# isg_cena_chip_wirebonding_board.net
KiCad netlist of a schematic drawn in Altium Designer
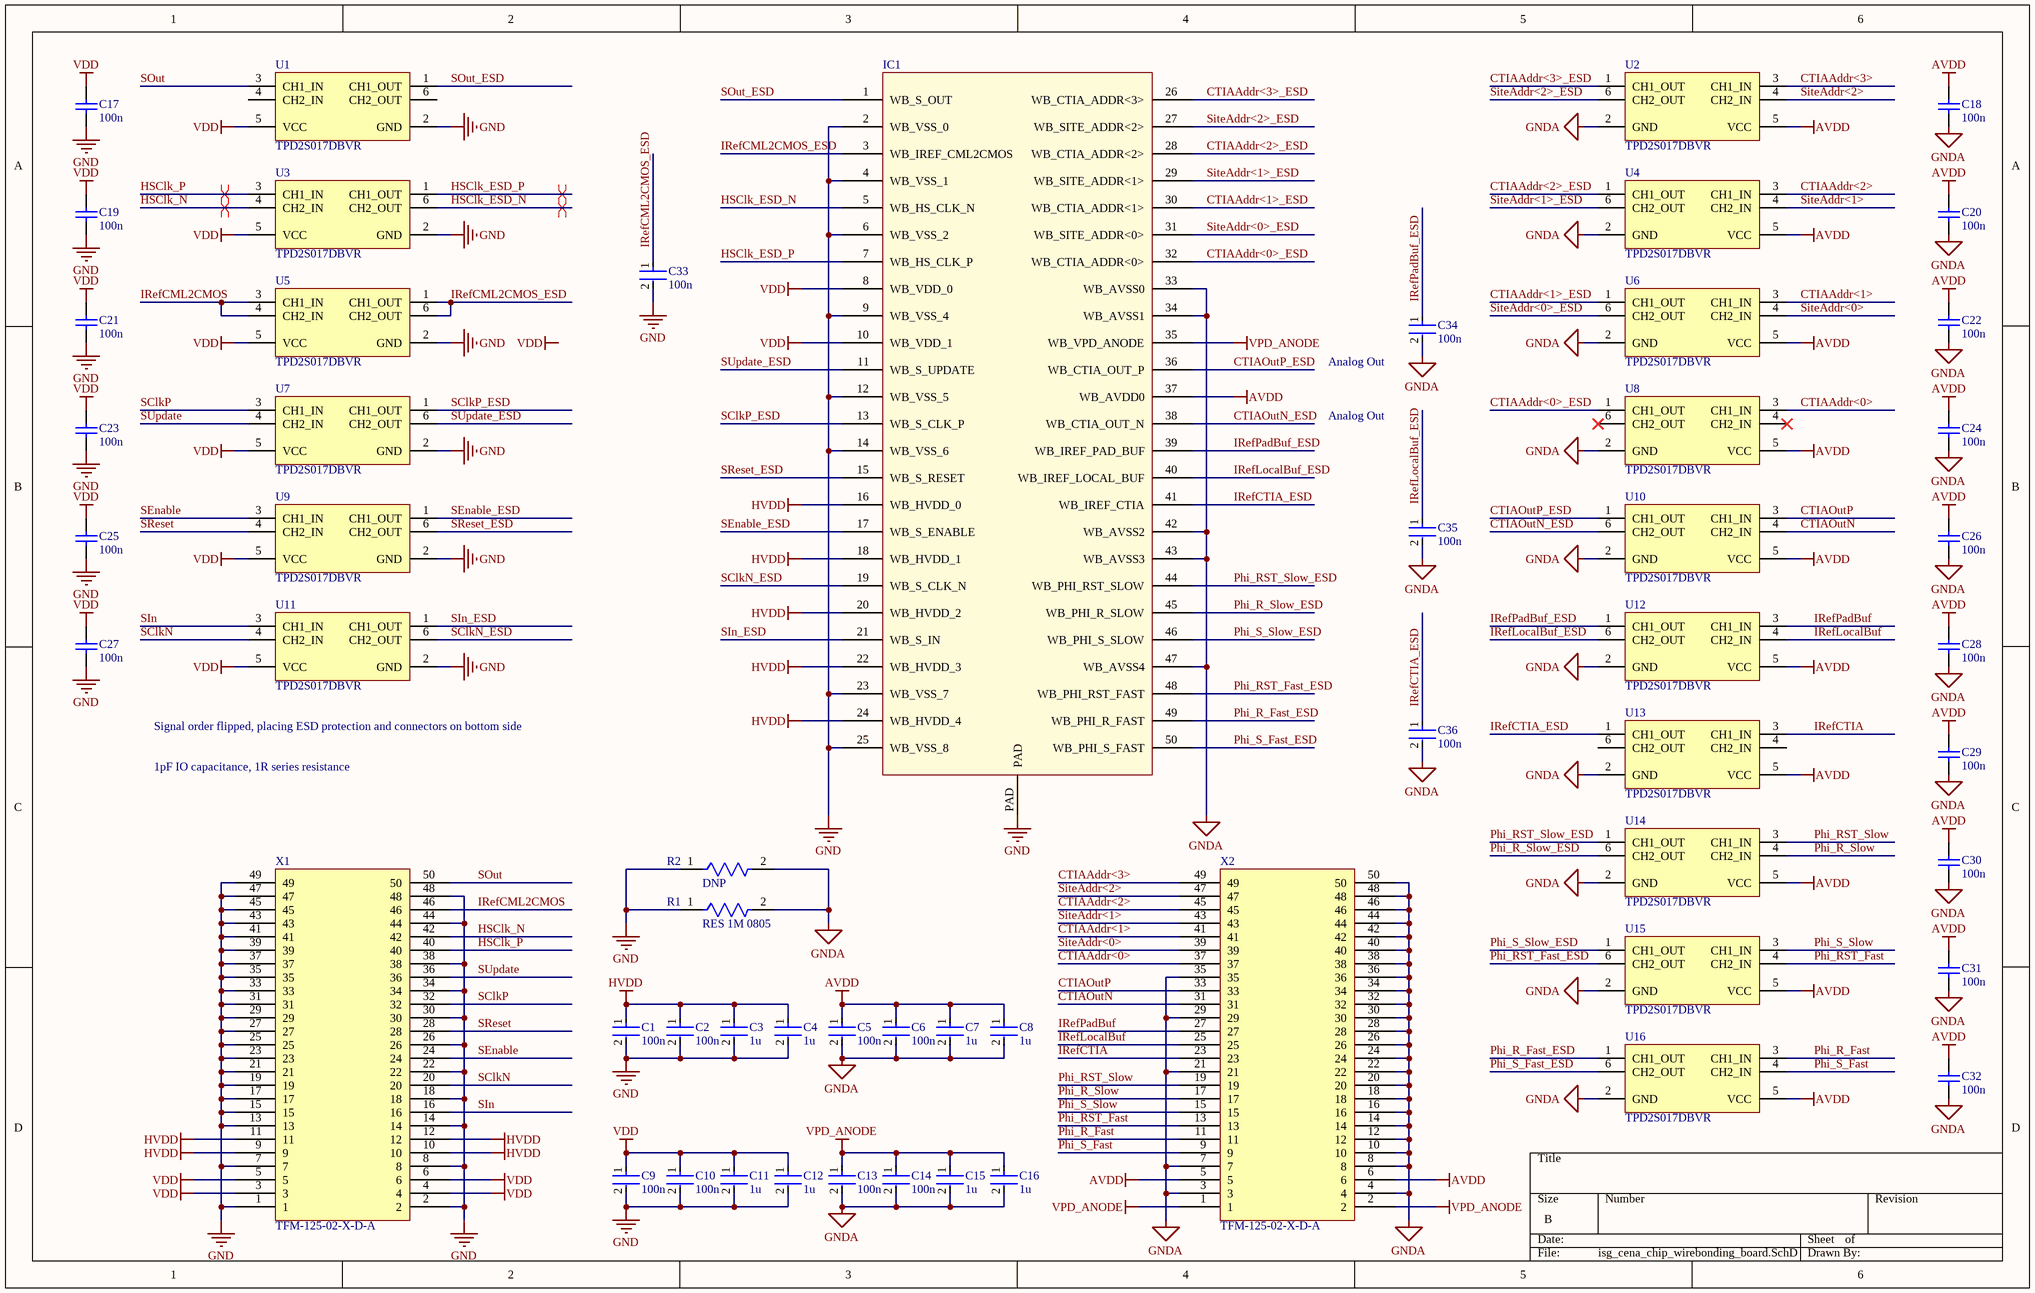
[diagram p0: isg_cena_chip_wirebonding_board.SchDoc]

(export (version "E")
  (design (tool "Eeschema 10.0.6"))
  (components
    (comp (ref "C1")
      (value "100n")
      (footprint "FP-0603-L_1_6_0_15-W_0_8-IPC_C")
      (description "Ceramic Capacitor General Use 1uF ±10% 50V X7R 0603")
      (fields (field (name "TOLERANCE") "10%"))
      (libsource (lib "Altium Content Vault") (part "11868f565c42a9108669ba33697ecf6"))
    )
    (comp (ref "C2")
      (value "100n")
      (footprint "FP-0603-L_1_6_0_15-W_0_8-IPC_C")
      (description "Ceramic Capacitor General Use 1uF ±10% 50V X7R 0603")
      (fields (field (name "TOLERANCE") "10%"))
      (libsource (lib "Altium Content Vault") (part "11868f565c42a9108669ba33697ecf6"))
    )
    (comp (ref "C3")
      (value "1u")
      (footprint "FP-0603-L_1_6_0_15-W_0_8-IPC_C")
      (description "Ceramic Capacitor General Use 1uF ±10% 50V X7R 0603")
      (fields (field (name "TOLERANCE") "10%"))
      (libsource (lib "Altium Content Vault") (part "11868f565c42a9108669ba33697ecf6"))
    )
    (comp (ref "C4")
      (value "1u")
      (footprint "FP-0603-L_1_6_0_15-W_0_8-IPC_C")
      (description "Ceramic Capacitor General Use 1uF ±10% 50V X7R 0603")
      (fields (field (name "TOLERANCE") "10%"))
      (libsource (lib "Altium Content Vault") (part "11868f565c42a9108669ba33697ecf6"))
    )
    (comp (ref "C5")
      (value "100n")
      (footprint "FP-0603-L_1_6_0_15-W_0_8-IPC_C")
      (description "Ceramic Capacitor General Use 1uF ±10% 50V X7R 0603")
      (fields (field (name "TOLERANCE") "10%"))
      (libsource (lib "Altium Content Vault") (part "11868f565c42a9108669ba33697ecf6"))
    )
    (comp (ref "C6")
      (value "100n")
      (footprint "FP-0603-L_1_6_0_15-W_0_8-IPC_C")
      (description "Ceramic Capacitor General Use 1uF ±10% 50V X7R 0603")
      (fields (field (name "TOLERANCE") "10%"))
      (libsource (lib "Altium Content Vault") (part "11868f565c42a9108669ba33697ecf6"))
    )
    (comp (ref "C7")
      (value "1u")
      (footprint "FP-0603-L_1_6_0_15-W_0_8-IPC_C")
      (description "Ceramic Capacitor General Use 1uF ±10% 50V X7R 0603")
      (fields (field (name "TOLERANCE") "10%"))
      (libsource (lib "Altium Content Vault") (part "11868f565c42a9108669ba33697ecf6"))
    )
    (comp (ref "C8")
      (value "1u")
      (footprint "FP-0603-L_1_6_0_15-W_0_8-IPC_C")
      (description "Ceramic Capacitor General Use 1uF ±10% 50V X7R 0603")
      (fields (field (name "TOLERANCE") "10%"))
      (libsource (lib "Altium Content Vault") (part "11868f565c42a9108669ba33697ecf6"))
    )
    (comp (ref "C9")
      (value "100n")
      (footprint "FP-0603-L_1_6_0_15-W_0_8-IPC_C")
      (description "Ceramic Capacitor General Use 1uF ±10% 50V X7R 0603")
      (fields (field (name "TOLERANCE") "10%"))
      (libsource (lib "Altium Content Vault") (part "11868f565c42a9108669ba33697ecf6"))
    )
    (comp (ref "C10")
      (value "100n")
      (footprint "FP-0603-L_1_6_0_15-W_0_8-IPC_C")
      (description "Ceramic Capacitor General Use 1uF ±10% 50V X7R 0603")
      (fields (field (name "TOLERANCE") "10%"))
      (libsource (lib "Altium Content Vault") (part "11868f565c42a9108669ba33697ecf6"))
    )
    (comp (ref "C11")
      (value "1u")
      (footprint "FP-0603-L_1_6_0_15-W_0_8-IPC_C")
      (description "Ceramic Capacitor General Use 1uF ±10% 50V X7R 0603")
      (fields (field (name "TOLERANCE") "10%"))
      (libsource (lib "Altium Content Vault") (part "11868f565c42a9108669ba33697ecf6"))
    )
    (comp (ref "C12")
      (value "1u")
      (footprint "FP-0603-L_1_6_0_15-W_0_8-IPC_C")
      (description "Ceramic Capacitor General Use 1uF ±10% 50V X7R 0603")
      (fields (field (name "TOLERANCE") "10%"))
      (libsource (lib "Altium Content Vault") (part "11868f565c42a9108669ba33697ecf6"))
    )
    (comp (ref "C13")
      (value "100n")
      (footprint "FP-0603-L_1_6_0_15-W_0_8-IPC_C")
      (description "Ceramic Capacitor General Use 1uF ±10% 50V X7R 0603")
      (fields (field (name "TOLERANCE") "10%"))
      (libsource (lib "Altium Content Vault") (part "11868f565c42a9108669ba33697ecf6"))
    )
    (comp (ref "C14")
      (value "100n")
      (footprint "FP-0603-L_1_6_0_15-W_0_8-IPC_C")
      (description "Ceramic Capacitor General Use 1uF ±10% 50V X7R 0603")
      (fields (field (name "TOLERANCE") "10%"))
      (libsource (lib "Altium Content Vault") (part "11868f565c42a9108669ba33697ecf6"))
    )
    (comp (ref "C15")
      (value "1u")
      (footprint "FP-0603-L_1_6_0_15-W_0_8-IPC_C")
      (description "Ceramic Capacitor General Use 1uF ±10% 50V X7R 0603")
      (fields (field (name "TOLERANCE") "10%"))
      (libsource (lib "Altium Content Vault") (part "11868f565c42a9108669ba33697ecf6"))
    )
    (comp (ref "C16")
      (value "1u")
      (footprint "FP-0603-L_1_6_0_15-W_0_8-IPC_C")
      (description "Ceramic Capacitor General Use 1uF ±10% 50V X7R 0603")
      (fields (field (name "TOLERANCE") "10%"))
      (libsource (lib "Altium Content Vault") (part "11868f565c42a9108669ba33697ecf6"))
    )
    (comp (ref "C17")
      (value "100n")
      (footprint "CAPC1050X55X23ML05T13")
      (description "Chip Capacitor, 100 nF, +/- 10%, 16 V, -55 to 125 degC, 0402 (1005 Metric), RoHS, Tape and Reel")
      (fields (field (name "MANUFACTURER") "Samsung Electro-Mechanics"))
      (libsource (lib "Altium Content Vault") (part "CAP-NP-2"))
    )
    (comp (ref "C18")
      (value "100n")
      (footprint "CAPC1050X55X23ML05T13")
      (description "Chip Capacitor, 100 nF, +/- 10%, 16 V, -55 to 125 degC, 0402 (1005 Metric), RoHS, Tape and Reel")
      (fields (field (name "MANUFACTURER") "Samsung Electro-Mechanics"))
      (libsource (lib "Altium Content Vault") (part "CAP-NP-2"))
    )
    (comp (ref "C19")
      (value "100n")
      (footprint "CAPC1050X55X23ML05T13")
      (description "Chip Capacitor, 100 nF, +/- 10%, 16 V, -55 to 125 degC, 0402 (1005 Metric), RoHS, Tape and Reel")
      (fields (field (name "MANUFACTURER") "Samsung Electro-Mechanics"))
      (libsource (lib "Altium Content Vault") (part "CAP-NP-2"))
    )
    (comp (ref "C20")
      (value "100n")
      (footprint "CAPC1050X55X23ML05T13")
      (description "Chip Capacitor, 100 nF, +/- 10%, 16 V, -55 to 125 degC, 0402 (1005 Metric), RoHS, Tape and Reel")
      (fields (field (name "MANUFACTURER") "Samsung Electro-Mechanics"))
      (libsource (lib "Altium Content Vault") (part "CAP-NP-2"))
    )
    (comp (ref "C21")
      (value "100n")
      (footprint "CAPC1050X55X23ML05T13")
      (description "Chip Capacitor, 100 nF, +/- 10%, 16 V, -55 to 125 degC, 0402 (1005 Metric), RoHS, Tape and Reel")
      (fields (field (name "MANUFACTURER") "Samsung Electro-Mechanics"))
      (libsource (lib "Altium Content Vault") (part "CAP-NP-2"))
    )
    (comp (ref "C22")
      (value "100n")
      (footprint "CAPC1050X55X23ML05T13")
      (description "Chip Capacitor, 100 nF, +/- 10%, 16 V, -55 to 125 degC, 0402 (1005 Metric), RoHS, Tape and Reel")
      (fields (field (name "MANUFACTURER") "Samsung Electro-Mechanics"))
      (libsource (lib "Altium Content Vault") (part "CAP-NP-2"))
    )
    (comp (ref "C23")
      (value "100n")
      (footprint "CAPC1050X55X23ML05T13")
      (description "Chip Capacitor, 100 nF, +/- 10%, 16 V, -55 to 125 degC, 0402 (1005 Metric), RoHS, Tape and Reel")
      (fields (field (name "MANUFACTURER") "Samsung Electro-Mechanics"))
      (libsource (lib "Altium Content Vault") (part "CAP-NP-2"))
    )
    (comp (ref "C24")
      (value "100n")
      (footprint "CAPC1050X55X23ML05T13")
      (description "Chip Capacitor, 100 nF, +/- 10%, 16 V, -55 to 125 degC, 0402 (1005 Metric), RoHS, Tape and Reel")
      (fields (field (name "MANUFACTURER") "Samsung Electro-Mechanics"))
      (libsource (lib "Altium Content Vault") (part "CAP-NP-2"))
    )
    (comp (ref "C25")
      (value "100n")
      (footprint "CAPC1050X55X23ML05T13")
      (description "Chip Capacitor, 100 nF, +/- 10%, 16 V, -55 to 125 degC, 0402 (1005 Metric), RoHS, Tape and Reel")
      (fields (field (name "MANUFACTURER") "Samsung Electro-Mechanics"))
      (libsource (lib "Altium Content Vault") (part "CAP-NP-2"))
    )
    (comp (ref "C26")
      (value "100n")
      (footprint "CAPC1050X55X23ML05T13")
      (description "Chip Capacitor, 100 nF, +/- 10%, 16 V, -55 to 125 degC, 0402 (1005 Metric), RoHS, Tape and Reel")
      (fields (field (name "MANUFACTURER") "Samsung Electro-Mechanics"))
      (libsource (lib "Altium Content Vault") (part "CAP-NP-2"))
    )
    (comp (ref "C27")
      (value "100n")
      (footprint "CAPC1050X55X23ML05T13")
      (description "Chip Capacitor, 100 nF, +/- 10%, 16 V, -55 to 125 degC, 0402 (1005 Metric), RoHS, Tape and Reel")
      (fields (field (name "MANUFACTURER") "Samsung Electro-Mechanics"))
      (libsource (lib "Altium Content Vault") (part "CAP-NP-2"))
    )
    (comp (ref "C28")
      (value "100n")
      (footprint "CAPC1050X55X23ML05T13")
      (description "Chip Capacitor, 100 nF, +/- 10%, 16 V, -55 to 125 degC, 0402 (1005 Metric), RoHS, Tape and Reel")
      (fields (field (name "MANUFACTURER") "Samsung Electro-Mechanics"))
      (libsource (lib "Altium Content Vault") (part "CAP-NP-2"))
    )
    (comp (ref "C29")
      (value "100n")
      (footprint "CAPC1050X55X23ML05T13")
      (description "Chip Capacitor, 100 nF, +/- 10%, 16 V, -55 to 125 degC, 0402 (1005 Metric), RoHS, Tape and Reel")
      (fields (field (name "MANUFACTURER") "Samsung Electro-Mechanics"))
      (libsource (lib "Altium Content Vault") (part "CAP-NP-2"))
    )
    (comp (ref "C30")
      (value "100n")
      (footprint "CAPC1050X55X23ML05T13")
      (description "Chip Capacitor, 100 nF, +/- 10%, 16 V, -55 to 125 degC, 0402 (1005 Metric), RoHS, Tape and Reel")
      (fields (field (name "MANUFACTURER") "Samsung Electro-Mechanics"))
      (libsource (lib "Altium Content Vault") (part "CAP-NP-2"))
    )
    (comp (ref "C31")
      (value "100n")
      (footprint "CAPC1050X55X23ML05T13")
      (description "Chip Capacitor, 100 nF, +/- 10%, 16 V, -55 to 125 degC, 0402 (1005 Metric), RoHS, Tape and Reel")
      (fields (field (name "MANUFACTURER") "Samsung Electro-Mechanics"))
      (libsource (lib "Altium Content Vault") (part "CAP-NP-2"))
    )
    (comp (ref "C32")
      (value "100n")
      (footprint "CAPC1050X55X23ML05T13")
      (description "Chip Capacitor, 100 nF, +/- 10%, 16 V, -55 to 125 degC, 0402 (1005 Metric), RoHS, Tape and Reel")
      (fields (field (name "MANUFACTURER") "Samsung Electro-Mechanics"))
      (libsource (lib "Altium Content Vault") (part "CAP-NP-2"))
    )
    (comp (ref "C33")
      (value "100n")
      (footprint "FP-0603-L_1_6_0_15-W_0_8-IPC_C")
      (description "Ceramic Capacitor General Use 1uF ±10% 50V X7R 0603")
      (fields (field (name "TOLERANCE") "10%"))
      (libsource (lib "Altium Content Vault") (part "11868f565c42a9108669ba33697ecf6"))
    )
    (comp (ref "C34")
      (value "100n")
      (footprint "FP-0603-L_1_6_0_15-W_0_8-IPC_C")
      (description "Ceramic Capacitor General Use 1uF ±10% 50V X7R 0603")
      (fields (field (name "TOLERANCE") "10%"))
      (libsource (lib "Altium Content Vault") (part "11868f565c42a9108669ba33697ecf6"))
    )
    (comp (ref "C35")
      (value "100n")
      (footprint "FP-0603-L_1_6_0_15-W_0_8-IPC_C")
      (description "Ceramic Capacitor General Use 1uF ±10% 50V X7R 0603")
      (fields (field (name "TOLERANCE") "10%"))
      (libsource (lib "Altium Content Vault") (part "11868f565c42a9108669ba33697ecf6"))
    )
    (comp (ref "C36")
      (value "100n")
      (footprint "FP-0603-L_1_6_0_15-W_0_8-IPC_C")
      (description "Ceramic Capacitor General Use 1uF ±10% 50V X7R 0603")
      (fields (field (name "TOLERANCE") "10%"))
      (libsource (lib "Altium Content Vault") (part "11868f565c42a9108669ba33697ecf6"))
    )
    (comp (ref "IC1") (value "~") (footprint "Cena_WB_4/4") (libsource (lib "CenaChip") (part "Cena")))
    (comp (ref "R1")
      (value "RES 1M 0805")
      (footprint "FP-ERJ6EN-IPC_A")
      (description "RES SMD 1M OHM 1% 1/8W 0805")
      (fields (field (name "TOLERANCE") "1%"))
      (libsource (lib "Altium Content Vault") (part "1029c3af85768c4190bb7ad29bc67b5"))
    )
    (comp (ref "R2")
      (value "DNP")
      (footprint "FP-ERJ6EN-IPC_A")
      (fields (field (name "TOLERANCE") "1%"))
      (libsource (lib "Altium Content Vault") (part "1029c3af85768c4190bb7ad29bc67b5"))
    )
    (comp (ref "U1")
      (value "TPD2S017DBVR")
      (footprint "DBV0006A_L")
      (fields (field (name "MANUFACTURER") "Texas Instruments"))
      (libsource (lib "") (part "TI-TPD2S017-SOT-23_DBV-6_1"))
    )
    (comp (ref "U2")
      (value "TPD2S017DBVR")
      (footprint "DBV0006A_L")
      (fields (field (name "MANUFACTURER") "Texas Instruments"))
      (libsource (lib "Altium Content Vault") (part "TI-TPD2S017-SOT-23_DBV-6"))
    )
    (comp (ref "U3")
      (value "TPD2S017DBVR")
      (footprint "DBV0006A_L")
      (fields (field (name "MANUFACTURER") "Texas Instruments"))
      (libsource (lib "") (part "TI-TPD2S017-SOT-23_DBV-6_1"))
    )
    (comp (ref "U4")
      (value "TPD2S017DBVR")
      (footprint "DBV0006A_L")
      (fields (field (name "MANUFACTURER") "Texas Instruments"))
      (libsource (lib "Altium Content Vault") (part "TI-TPD2S017-SOT-23_DBV-6"))
    )
    (comp (ref "U5")
      (value "TPD2S017DBVR")
      (footprint "DBV0006A_L")
      (fields (field (name "MANUFACTURER") "Texas Instruments"))
      (libsource (lib "") (part "TI-TPD2S017-SOT-23_DBV-6_1"))
    )
    (comp (ref "U6")
      (value "TPD2S017DBVR")
      (footprint "DBV0006A_L")
      (fields (field (name "MANUFACTURER") "Texas Instruments"))
      (libsource (lib "Altium Content Vault") (part "TI-TPD2S017-SOT-23_DBV-6"))
    )
    (comp (ref "U7")
      (value "TPD2S017DBVR")
      (footprint "DBV0006A_L")
      (fields (field (name "MANUFACTURER") "Texas Instruments"))
      (libsource (lib "") (part "TI-TPD2S017-SOT-23_DBV-6_1"))
    )
    (comp (ref "U8")
      (value "TPD2S017DBVR")
      (footprint "DBV0006A_L")
      (fields (field (name "MANUFACTURER") "Texas Instruments"))
      (libsource (lib "Altium Content Vault") (part "TI-TPD2S017-SOT-23_DBV-6"))
    )
    (comp (ref "U9")
      (value "TPD2S017DBVR")
      (footprint "DBV0006A_L")
      (fields (field (name "MANUFACTURER") "Texas Instruments"))
      (libsource (lib "") (part "TI-TPD2S017-SOT-23_DBV-6_1"))
    )
    (comp (ref "U10")
      (value "TPD2S017DBVR")
      (footprint "DBV0006A_L")
      (fields (field (name "MANUFACTURER") "Texas Instruments"))
      (libsource (lib "Altium Content Vault") (part "TI-TPD2S017-SOT-23_DBV-6"))
    )
    (comp (ref "U11")
      (value "TPD2S017DBVR")
      (footprint "DBV0006A_L")
      (fields (field (name "MANUFACTURER") "Texas Instruments"))
      (libsource (lib "") (part "TI-TPD2S017-SOT-23_DBV-6_1"))
    )
    (comp (ref "U12")
      (value "TPD2S017DBVR")
      (footprint "DBV0006A_L")
      (fields (field (name "MANUFACTURER") "Texas Instruments"))
      (libsource (lib "Altium Content Vault") (part "TI-TPD2S017-SOT-23_DBV-6"))
    )
    (comp (ref "U13")
      (value "TPD2S017DBVR")
      (footprint "DBV0006A_L")
      (fields (field (name "MANUFACTURER") "Texas Instruments"))
      (libsource (lib "Altium Content Vault") (part "TI-TPD2S017-SOT-23_DBV-6"))
    )
    (comp (ref "U14")
      (value "TPD2S017DBVR")
      (footprint "DBV0006A_L")
      (fields (field (name "MANUFACTURER") "Texas Instruments"))
      (libsource (lib "Altium Content Vault") (part "TI-TPD2S017-SOT-23_DBV-6"))
    )
    (comp (ref "U15")
      (value "TPD2S017DBVR")
      (footprint "DBV0006A_L")
      (fields (field (name "MANUFACTURER") "Texas Instruments"))
      (libsource (lib "Altium Content Vault") (part "TI-TPD2S017-SOT-23_DBV-6"))
    )
    (comp (ref "U16")
      (value "TPD2S017DBVR")
      (footprint "DBV0006A_L")
      (fields (field (name "MANUFACTURER") "Texas Instruments"))
      (libsource (lib "Altium Content Vault") (part "TI-TPD2S017-SOT-23_DBV-6"))
    )
    (comp (ref "X1")
      (value "TFM-125-02-X-D-A")
      (footprint "SAMTEC-TFM-125-02-X-D-A")
      (description "SAMTEC TFM-125-02-X-D-A")
      (libsource (lib "SAMTEC-TFM-125-02-X-D-A") (part "TFM-125-02-X-D-A"))
    )
    (comp (ref "X2")
      (value "TFM-125-02-X-D-A")
      (footprint "SAMTEC-TFM-125-02-X-D-A")
      (description "SAMTEC TFM-125-02-X-D-A")
      (libsource (lib "SAMTEC-TFM-125-02-X-D-A") (part "TFM-125-02-X-D-A"))
    )
  )
  (nets
    (net (code "1") (name "/CTIAAddr<0>") (class "Default")
      (node (ref "U8") (pin "3") (pinfunction "CH1_IN_3") (pintype "passive"))
      (node (ref "X2") (pin "37") (pinfunction "37_37") (pintype "passive"))
    )
    (net (code "2") (name "/CTIAAddr<0>_ESD") (class "Default")
      (node (ref "IC1") (pin "32") (pinfunction "WB_CTIA_ADDR<0>_32") (pintype "passive"))
      (node (ref "U8") (pin "1") (pinfunction "CH1_OUT_1") (pintype "passive"))
    )
    (net (code "3") (name "/CTIAAddr<1>") (class "Default")
      (node (ref "U6") (pin "3") (pinfunction "CH1_IN_3") (pintype "passive"))
      (node (ref "X2") (pin "41") (pinfunction "41_41") (pintype "passive"))
    )
    (net (code "4") (name "/CTIAAddr<1>_ESD") (class "Default")
      (node (ref "IC1") (pin "30") (pinfunction "WB_CTIA_ADDR<1>_30") (pintype "passive"))
      (node (ref "U6") (pin "1") (pinfunction "CH1_OUT_1") (pintype "passive"))
    )
    (net (code "5") (name "/CTIAAddr<2>") (class "Default")
      (node (ref "U4") (pin "3") (pinfunction "CH1_IN_3") (pintype "passive"))
      (node (ref "X2") (pin "45") (pinfunction "45_45") (pintype "passive"))
    )
    (net (code "6") (name "/CTIAAddr<2>_ESD") (class "Default")
      (node (ref "IC1") (pin "28") (pinfunction "WB_CTIA_ADDR<2>_28") (pintype "passive"))
      (node (ref "U4") (pin "1") (pinfunction "CH1_OUT_1") (pintype "passive"))
    )
    (net (code "7") (name "/CTIAAddr<3>") (class "Default")
      (node (ref "U2") (pin "3") (pinfunction "CH1_IN_3") (pintype "passive"))
      (node (ref "X2") (pin "49") (pinfunction "49_49") (pintype "passive"))
    )
    (net (code "8") (name "/CTIAAddr<3>_ESD") (class "Default")
      (node (ref "IC1") (pin "26") (pinfunction "WB_CTIA_ADDR<3>_26") (pintype "passive"))
      (node (ref "U2") (pin "1") (pinfunction "CH1_OUT_1") (pintype "passive"))
    )
    (net (code "9") (name "/CTIAOutN") (class "Default")
      (node (ref "U10") (pin "4") (pinfunction "CH2_IN_4") (pintype "passive"))
      (node (ref "X2") (pin "31") (pinfunction "31_31") (pintype "passive"))
    )
    (net (code "10") (name "/CTIAOutN_ESD") (class "Default")
      (node (ref "IC1") (pin "38") (pinfunction "WB_CTIA_OUT_N_38") (pintype "passive"))
      (node (ref "U10") (pin "6") (pinfunction "CH2_OUT_6") (pintype "passive"))
    )
    (net (code "11") (name "/CTIAOutP") (class "Default")
      (node (ref "U10") (pin "3") (pinfunction "CH1_IN_3") (pintype "passive"))
      (node (ref "X2") (pin "33") (pinfunction "33_33") (pintype "passive"))
    )
    (net (code "12") (name "/CTIAOutP_ESD") (class "Default")
      (node (ref "IC1") (pin "36") (pinfunction "WB_CTIA_OUT_P_36") (pintype "passive"))
      (node (ref "U10") (pin "1") (pinfunction "CH1_OUT_1") (pintype "passive"))
    )
    (net (code "13") (name "/HSClk_ESD_N") (class "Default")
      (node (ref "IC1") (pin "5") (pinfunction "WB_HS_CLK_N_5") (pintype "passive"))
      (node (ref "U3") (pin "6") (pinfunction "CH2_OUT_6") (pintype "passive"))
    )
    (net (code "14") (name "/HSClk_ESD_P") (class "Default")
      (node (ref "IC1") (pin "7") (pinfunction "WB_HS_CLK_P_7") (pintype "passive"))
      (node (ref "U3") (pin "1") (pinfunction "CH1_OUT_1") (pintype "passive"))
    )
    (net (code "15") (name "/HSClk_N") (class "Default")
      (node (ref "U3") (pin "4") (pinfunction "CH2_IN_4") (pintype "passive"))
      (node (ref "X1") (pin "42") (pinfunction "42_42") (pintype "passive"))
    )
    (net (code "16") (name "/HSClk_P") (class "Default")
      (node (ref "U3") (pin "3") (pinfunction "CH1_IN_3") (pintype "passive"))
      (node (ref "X1") (pin "40") (pinfunction "40_40") (pintype "passive"))
    )
    (net (code "17") (name "/IRefCML2CMOS") (class "Default")
      (node (ref "U5") (pin "3") (pinfunction "CH1_IN_3") (pintype "passive"))
      (node (ref "U5") (pin "4") (pinfunction "CH2_IN_4") (pintype "passive"))
      (node (ref "X1") (pin "46") (pinfunction "46_46") (pintype "passive"))
    )
    (net (code "18") (name "/IRefCML2CMOS_ESD") (class "Default")
      (node (ref "C33") (pin "1") (pinfunction "1_1") (pintype "passive"))
      (node (ref "IC1") (pin "3") (pinfunction "WB_IREF_CML2CMOS_3") (pintype "passive"))
      (node (ref "U5") (pin "1") (pinfunction "CH1_OUT_1") (pintype "passive"))
      (node (ref "U5") (pin "6") (pinfunction "CH2_OUT_6") (pintype "passive"))
    )
    (net (code "19") (name "/IRefCTIA") (class "Default")
      (node (ref "U13") (pin "3") (pinfunction "CH1_IN_3") (pintype "passive"))
      (node (ref "X2") (pin "23") (pinfunction "23_23") (pintype "passive"))
    )
    (net (code "20") (name "/IRefCTIA_ESD") (class "Default")
      (node (ref "C36") (pin "1") (pinfunction "1_1") (pintype "passive"))
      (node (ref "IC1") (pin "41") (pinfunction "WB_IREF_CTIA_41") (pintype "passive"))
      (node (ref "U13") (pin "1") (pinfunction "CH1_OUT_1") (pintype "passive"))
    )
    (net (code "21") (name "/IRefLocalBuf") (class "Default")
      (node (ref "U12") (pin "4") (pinfunction "CH2_IN_4") (pintype "passive"))
      (node (ref "X2") (pin "25") (pinfunction "25_25") (pintype "passive"))
    )
    (net (code "22") (name "/IRefLocalBuf_ESD") (class "Default")
      (node (ref "C35") (pin "1") (pinfunction "1_1") (pintype "passive"))
      (node (ref "IC1") (pin "40") (pinfunction "WB_IREF_LOCAL_BUF_40") (pintype "passive"))
      (node (ref "U12") (pin "6") (pinfunction "CH2_OUT_6") (pintype "passive"))
    )
    (net (code "23") (name "/IRefPadBuf") (class "Default")
      (node (ref "U12") (pin "3") (pinfunction "CH1_IN_3") (pintype "passive"))
      (node (ref "X2") (pin "27") (pinfunction "27_27") (pintype "passive"))
    )
    (net (code "24") (name "/IRefPadBuf_ESD") (class "Default")
      (node (ref "C34") (pin "1") (pinfunction "1_1") (pintype "passive"))
      (node (ref "IC1") (pin "39") (pinfunction "WB_IREF_PAD_BUF_39") (pintype "passive"))
      (node (ref "U12") (pin "1") (pinfunction "CH1_OUT_1") (pintype "passive"))
    )
    (net (code "25") (name "/Phi_RST_Fast") (class "Default")
      (node (ref "U15") (pin "4") (pinfunction "CH2_IN_4") (pintype "passive"))
      (node (ref "X2") (pin "13") (pinfunction "13_13") (pintype "passive"))
    )
    (net (code "26") (name "/Phi_RST_Fast_ESD") (class "Default")
      (node (ref "IC1") (pin "48") (pinfunction "WB_PHI_RST_FAST_48") (pintype "passive"))
      (node (ref "U15") (pin "6") (pinfunction "CH2_OUT_6") (pintype "passive"))
    )
    (net (code "27") (name "/Phi_RST_Slow") (class "Default")
      (node (ref "U14") (pin "3") (pinfunction "CH1_IN_3") (pintype "passive"))
      (node (ref "X2") (pin "19") (pinfunction "19_19") (pintype "passive"))
    )
    (net (code "28") (name "/Phi_RST_Slow_ESD") (class "Default")
      (node (ref "IC1") (pin "44") (pinfunction "WB_PHI_RST_SLOW_44") (pintype "passive"))
      (node (ref "U14") (pin "1") (pinfunction "CH1_OUT_1") (pintype "passive"))
    )
    (net (code "29") (name "/Phi_R_Fast") (class "Default")
      (node (ref "U16") (pin "3") (pinfunction "CH1_IN_3") (pintype "passive"))
      (node (ref "X2") (pin "11") (pinfunction "11_11") (pintype "passive"))
    )
    (net (code "30") (name "/Phi_R_Fast_ESD") (class "Default")
      (node (ref "IC1") (pin "49") (pinfunction "WB_PHI_R_FAST_49") (pintype "passive"))
      (node (ref "U16") (pin "1") (pinfunction "CH1_OUT_1") (pintype "passive"))
    )
    (net (code "31") (name "/Phi_R_Slow") (class "Default")
      (node (ref "U14") (pin "4") (pinfunction "CH2_IN_4") (pintype "passive"))
      (node (ref "X2") (pin "17") (pinfunction "17_17") (pintype "passive"))
    )
    (net (code "32") (name "/Phi_R_Slow_ESD") (class "Default")
      (node (ref "IC1") (pin "45") (pinfunction "WB_PHI_R_SLOW_45") (pintype "passive"))
      (node (ref "U14") (pin "6") (pinfunction "CH2_OUT_6") (pintype "passive"))
    )
    (net (code "33") (name "/Phi_S_Fast") (class "Default")
      (node (ref "U16") (pin "4") (pinfunction "CH2_IN_4") (pintype "passive"))
      (node (ref "X2") (pin "9") (pinfunction "9_9") (pintype "passive"))
    )
    (net (code "34") (name "/Phi_S_Fast_ESD") (class "Default")
      (node (ref "IC1") (pin "50") (pinfunction "WB_PHI_S_FAST_50") (pintype "passive"))
      (node (ref "U16") (pin "6") (pinfunction "CH2_OUT_6") (pintype "passive"))
    )
    (net (code "35") (name "/Phi_S_Slow") (class "Default")
      (node (ref "U15") (pin "3") (pinfunction "CH1_IN_3") (pintype "passive"))
      (node (ref "X2") (pin "15") (pinfunction "15_15") (pintype "passive"))
    )
    (net (code "36") (name "/Phi_S_Slow_ESD") (class "Default")
      (node (ref "IC1") (pin "46") (pinfunction "WB_PHI_S_SLOW_46") (pintype "passive"))
      (node (ref "U15") (pin "1") (pinfunction "CH1_OUT_1") (pintype "passive"))
    )
    (net (code "37") (name "/SClkN") (class "Default")
      (node (ref "U11") (pin "4") (pinfunction "CH2_IN_4") (pintype "passive"))
      (node (ref "X1") (pin "20") (pinfunction "20_20") (pintype "passive"))
    )
    (net (code "38") (name "/SClkN_ESD") (class "Default")
      (node (ref "IC1") (pin "19") (pinfunction "WB_S_CLK_N_19") (pintype "passive"))
      (node (ref "U11") (pin "6") (pinfunction "CH2_OUT_6") (pintype "passive"))
    )
    (net (code "39") (name "/SClkP") (class "Default")
      (node (ref "U7") (pin "3") (pinfunction "CH1_IN_3") (pintype "passive"))
      (node (ref "X1") (pin "32") (pinfunction "32_32") (pintype "passive"))
    )
    (net (code "40") (name "/SClkP_ESD") (class "Default")
      (node (ref "IC1") (pin "13") (pinfunction "WB_S_CLK_P_13") (pintype "passive"))
      (node (ref "U7") (pin "1") (pinfunction "CH1_OUT_1") (pintype "passive"))
    )
    (net (code "41") (name "/SEnable") (class "Default")
      (node (ref "U9") (pin "3") (pinfunction "CH1_IN_3") (pintype "passive"))
      (node (ref "X1") (pin "24") (pinfunction "24_24") (pintype "passive"))
    )
    (net (code "42") (name "/SEnable_ESD") (class "Default")
      (node (ref "IC1") (pin "17") (pinfunction "WB_S_ENABLE_17") (pintype "passive"))
      (node (ref "U9") (pin "1") (pinfunction "CH1_OUT_1") (pintype "passive"))
    )
    (net (code "43") (name "/SIn") (class "Default")
      (node (ref "U11") (pin "3") (pinfunction "CH1_IN_3") (pintype "passive"))
      (node (ref "X1") (pin "16") (pinfunction "16_16") (pintype "passive"))
    )
    (net (code "44") (name "/SIn_ESD") (class "Default")
      (node (ref "IC1") (pin "21") (pinfunction "WB_S_IN_21") (pintype "passive"))
      (node (ref "U11") (pin "1") (pinfunction "CH1_OUT_1") (pintype "passive"))
    )
    (net (code "45") (name "/SOut") (class "Default")
      (node (ref "U1") (pin "3") (pinfunction "CH1_IN_3") (pintype "passive"))
      (node (ref "X1") (pin "50") (pinfunction "50_50") (pintype "passive"))
    )
    (net (code "46") (name "/SOut_ESD") (class "Default")
      (node (ref "IC1") (pin "1") (pinfunction "WB_S_OUT_1") (pintype "passive"))
      (node (ref "U1") (pin "1") (pinfunction "CH1_OUT_1") (pintype "passive"))
    )
    (net (code "47") (name "/SReset") (class "Default")
      (node (ref "U9") (pin "4") (pinfunction "CH2_IN_4") (pintype "passive"))
      (node (ref "X1") (pin "28") (pinfunction "28_28") (pintype "passive"))
    )
    (net (code "48") (name "/SReset_ESD") (class "Default")
      (node (ref "IC1") (pin "15") (pinfunction "WB_S_RESET_15") (pintype "passive"))
      (node (ref "U9") (pin "6") (pinfunction "CH2_OUT_6") (pintype "passive"))
    )
    (net (code "49") (name "/SUpdate") (class "Default")
      (node (ref "U7") (pin "4") (pinfunction "CH2_IN_4") (pintype "passive"))
      (node (ref "X1") (pin "36") (pinfunction "36_36") (pintype "passive"))
    )
    (net (code "50") (name "/SUpdate_ESD") (class "Default")
      (node (ref "IC1") (pin "11") (pinfunction "WB_S_UPDATE_11") (pintype "passive"))
      (node (ref "U7") (pin "6") (pinfunction "CH2_OUT_6") (pintype "passive"))
    )
    (net (code "51") (name "/SiteAddr<0>") (class "Default")
      (node (ref "U6") (pin "4") (pinfunction "CH2_IN_4") (pintype "passive"))
      (node (ref "X2") (pin "39") (pinfunction "39_39") (pintype "passive"))
    )
    (net (code "52") (name "/SiteAddr<0>_ESD") (class "Default")
      (node (ref "IC1") (pin "31") (pinfunction "WB_SITE_ADDR<0>_31") (pintype "passive"))
      (node (ref "U6") (pin "6") (pinfunction "CH2_OUT_6") (pintype "passive"))
    )
    (net (code "53") (name "/SiteAddr<1>") (class "Default")
      (node (ref "U4") (pin "4") (pinfunction "CH2_IN_4") (pintype "passive"))
      (node (ref "X2") (pin "43") (pinfunction "43_43") (pintype "passive"))
    )
    (net (code "54") (name "/SiteAddr<1>_ESD") (class "Default")
      (node (ref "IC1") (pin "29") (pinfunction "WB_SITE_ADDR<1>_29") (pintype "passive"))
      (node (ref "U4") (pin "6") (pinfunction "CH2_OUT_6") (pintype "passive"))
    )
    (net (code "55") (name "/SiteAddr<2>") (class "Default")
      (node (ref "U2") (pin "4") (pinfunction "CH2_IN_4") (pintype "passive"))
      (node (ref "X2") (pin "47") (pinfunction "47_47") (pintype "passive"))
    )
    (net (code "56") (name "/SiteAddr<2>_ESD") (class "Default")
      (node (ref "IC1") (pin "27") (pinfunction "WB_SITE_ADDR<2>_27") (pintype "passive"))
      (node (ref "U2") (pin "6") (pinfunction "CH2_OUT_6") (pintype "passive"))
    )
    (net (code "57") (name "AVDD") (class "Default")
      (node (ref "C18") (pin "1") (pinfunction "1_1") (pintype "passive"))
      (node (ref "C20") (pin "1") (pinfunction "1_1") (pintype "passive"))
      (node (ref "C22") (pin "1") (pinfunction "1_1") (pintype "passive"))
      (node (ref "C24") (pin "1") (pinfunction "1_1") (pintype "passive"))
      (node (ref "C26") (pin "1") (pinfunction "1_1") (pintype "passive"))
      (node (ref "C28") (pin "1") (pinfunction "1_1") (pintype "passive"))
      (node (ref "C29") (pin "1") (pinfunction "1_1") (pintype "passive"))
      (node (ref "C30") (pin "1") (pinfunction "1_1") (pintype "passive"))
      (node (ref "C31") (pin "1") (pinfunction "1_1") (pintype "passive"))
      (node (ref "C32") (pin "1") (pinfunction "1_1") (pintype "passive"))
      (node (ref "C5") (pin "1") (pinfunction "1_1") (pintype "passive"))
      (node (ref "C6") (pin "1") (pinfunction "1_1") (pintype "passive"))
      (node (ref "C7") (pin "1") (pinfunction "1_1") (pintype "passive"))
      (node (ref "C8") (pin "1") (pinfunction "1_1") (pintype "passive"))
      (node (ref "IC1") (pin "37") (pinfunction "WB_AVDD0_37") (pintype "passive"))
      (node (ref "U10") (pin "5") (pinfunction "VCC_5") (pintype "power_in"))
      (node (ref "U12") (pin "5") (pinfunction "VCC_5") (pintype "power_in"))
      (node (ref "U13") (pin "5") (pinfunction "VCC_5") (pintype "power_in"))
      (node (ref "U14") (pin "5") (pinfunction "VCC_5") (pintype "power_in"))
      (node (ref "U15") (pin "5") (pinfunction "VCC_5") (pintype "power_in"))
      (node (ref "U16") (pin "5") (pinfunction "VCC_5") (pintype "power_in"))
      (node (ref "U2") (pin "5") (pinfunction "VCC_5") (pintype "power_in"))
      (node (ref "U4") (pin "5") (pinfunction "VCC_5") (pintype "power_in"))
      (node (ref "U6") (pin "5") (pinfunction "VCC_5") (pintype "power_in"))
      (node (ref "U8") (pin "5") (pinfunction "VCC_5") (pintype "power_in"))
      (node (ref "X2") (pin "5") (pinfunction "5_5") (pintype "passive"))
      (node (ref "X2") (pin "6") (pinfunction "6_6") (pintype "passive"))
    )
    (net (code "58") (name "GND") (class "Default")
      (node (ref "C1") (pin "2") (pinfunction "2_2") (pintype "passive"))
      (node (ref "C10") (pin "2") (pinfunction "2_2") (pintype "passive"))
      (node (ref "C11") (pin "2") (pinfunction "2_2") (pintype "passive"))
      (node (ref "C12") (pin "2") (pinfunction "2_2") (pintype "passive"))
      (node (ref "C17") (pin "2") (pinfunction "2_2") (pintype "passive"))
      (node (ref "C19") (pin "2") (pinfunction "2_2") (pintype "passive"))
      (node (ref "C2") (pin "2") (pinfunction "2_2") (pintype "passive"))
      (node (ref "C21") (pin "2") (pinfunction "2_2") (pintype "passive"))
      (node (ref "C23") (pin "2") (pinfunction "2_2") (pintype "passive"))
      (node (ref "C25") (pin "2") (pinfunction "2_2") (pintype "passive"))
      (node (ref "C27") (pin "2") (pinfunction "2_2") (pintype "passive"))
      (node (ref "C3") (pin "2") (pinfunction "2_2") (pintype "passive"))
      (node (ref "C33") (pin "2") (pinfunction "2_2") (pintype "passive"))
      (node (ref "C4") (pin "2") (pinfunction "2_2") (pintype "passive"))
      (node (ref "C9") (pin "2") (pinfunction "2_2") (pintype "passive"))
      (node (ref "IC1") (pin "12") (pinfunction "WB_VSS_5_12") (pintype "passive"))
      (node (ref "IC1") (pin "14") (pinfunction "WB_VSS_6_14") (pintype "passive"))
      (node (ref "IC1") (pin "2") (pinfunction "WB_VSS_0_2") (pintype "passive"))
      (node (ref "IC1") (pin "23") (pinfunction "WB_VSS_7_23") (pintype "passive"))
      (node (ref "IC1") (pin "25") (pinfunction "WB_VSS_8_25") (pintype "passive"))
      (node (ref "IC1") (pin "4") (pinfunction "WB_VSS_1_4") (pintype "passive"))
      (node (ref "IC1") (pin "6") (pinfunction "WB_VSS_2_6") (pintype "passive"))
      (node (ref "IC1") (pin "9") (pinfunction "WB_VSS_4_9") (pintype "passive"))
      (node (ref "IC1") (pin "PAD") (pinfunction "PAD_PAD") (pintype "passive"))
      (node (ref "R1") (pin "1") (pinfunction "1_1") (pintype "passive"))
      (node (ref "R2") (pin "1") (pinfunction "1_1") (pintype "passive"))
      (node (ref "U1") (pin "2") (pinfunction "GND_2") (pintype "power_in"))
      (node (ref "U11") (pin "2") (pinfunction "GND_2") (pintype "power_in"))
      (node (ref "U3") (pin "2") (pinfunction "GND_2") (pintype "power_in"))
      (node (ref "U5") (pin "2") (pinfunction "GND_2") (pintype "power_in"))
      (node (ref "U7") (pin "2") (pinfunction "GND_2") (pintype "power_in"))
      (node (ref "U9") (pin "2") (pinfunction "GND_2") (pintype "power_in"))
      (node (ref "X1") (pin "1") (pinfunction "1_1") (pintype "passive"))
      (node (ref "X1") (pin "13") (pinfunction "13_13") (pintype "passive"))
      (node (ref "X1") (pin "14") (pinfunction "14_14") (pintype "passive"))
      (node (ref "X1") (pin "15") (pinfunction "15_15") (pintype "passive"))
      (node (ref "X1") (pin "17") (pinfunction "17_17") (pintype "passive"))
      (node (ref "X1") (pin "18") (pinfunction "18_18") (pintype "passive"))
      (node (ref "X1") (pin "19") (pinfunction "19_19") (pintype "passive"))
      (node (ref "X1") (pin "2") (pinfunction "2_2") (pintype "passive"))
      (node (ref "X1") (pin "21") (pinfunction "21_21") (pintype "passive"))
      (node (ref "X1") (pin "22") (pinfunction "22_22") (pintype "passive"))
      (node (ref "X1") (pin "23") (pinfunction "23_23") (pintype "passive"))
      (node (ref "X1") (pin "25") (pinfunction "25_25") (pintype "passive"))
      (node (ref "X1") (pin "26") (pinfunction "26_26") (pintype "passive"))
      (node (ref "X1") (pin "27") (pinfunction "27_27") (pintype "passive"))
      (node (ref "X1") (pin "29") (pinfunction "29_29") (pintype "passive"))
      (node (ref "X1") (pin "30") (pinfunction "30_30") (pintype "passive"))
      (node (ref "X1") (pin "31") (pinfunction "31_31") (pintype "passive"))
      (node (ref "X1") (pin "33") (pinfunction "33_33") (pintype "passive"))
      (node (ref "X1") (pin "34") (pinfunction "34_34") (pintype "passive"))
      (node (ref "X1") (pin "35") (pinfunction "35_35") (pintype "passive"))
      (node (ref "X1") (pin "37") (pinfunction "37_37") (pintype "passive"))
      (node (ref "X1") (pin "38") (pinfunction "38_38") (pintype "passive"))
      (node (ref "X1") (pin "39") (pinfunction "39_39") (pintype "passive"))
      (node (ref "X1") (pin "41") (pinfunction "41_41") (pintype "passive"))
      (node (ref "X1") (pin "43") (pinfunction "43_43") (pintype "passive"))
      (node (ref "X1") (pin "44") (pinfunction "44_44") (pintype "passive"))
      (node (ref "X1") (pin "45") (pinfunction "45_45") (pintype "passive"))
      (node (ref "X1") (pin "47") (pinfunction "47_47") (pintype "passive"))
      (node (ref "X1") (pin "48") (pinfunction "48_48") (pintype "passive"))
      (node (ref "X1") (pin "49") (pinfunction "49_49") (pintype "passive"))
      (node (ref "X1") (pin "7") (pinfunction "7_7") (pintype "passive"))
      (node (ref "X1") (pin "8") (pinfunction "8_8") (pintype "passive"))
    )
    (net (code "59") (name "GNDA") (class "Default")
      (node (ref "C13") (pin "2") (pinfunction "2_2") (pintype "passive"))
      (node (ref "C14") (pin "2") (pinfunction "2_2") (pintype "passive"))
      (node (ref "C15") (pin "2") (pinfunction "2_2") (pintype "passive"))
      (node (ref "C16") (pin "2") (pinfunction "2_2") (pintype "passive"))
      (node (ref "C18") (pin "2") (pinfunction "2_2") (pintype "passive"))
      (node (ref "C20") (pin "2") (pinfunction "2_2") (pintype "passive"))
      (node (ref "C22") (pin "2") (pinfunction "2_2") (pintype "passive"))
      (node (ref "C24") (pin "2") (pinfunction "2_2") (pintype "passive"))
      (node (ref "C26") (pin "2") (pinfunction "2_2") (pintype "passive"))
      (node (ref "C28") (pin "2") (pinfunction "2_2") (pintype "passive"))
      (node (ref "C29") (pin "2") (pinfunction "2_2") (pintype "passive"))
      (node (ref "C30") (pin "2") (pinfunction "2_2") (pintype "passive"))
      (node (ref "C31") (pin "2") (pinfunction "2_2") (pintype "passive"))
      (node (ref "C32") (pin "2") (pinfunction "2_2") (pintype "passive"))
      (node (ref "C34") (pin "2") (pinfunction "2_2") (pintype "passive"))
      (node (ref "C35") (pin "2") (pinfunction "2_2") (pintype "passive"))
      (node (ref "C36") (pin "2") (pinfunction "2_2") (pintype "passive"))
      (node (ref "C5") (pin "2") (pinfunction "2_2") (pintype "passive"))
      (node (ref "C6") (pin "2") (pinfunction "2_2") (pintype "passive"))
      (node (ref "C7") (pin "2") (pinfunction "2_2") (pintype "passive"))
      (node (ref "C8") (pin "2") (pinfunction "2_2") (pintype "passive"))
      (node (ref "IC1") (pin "33") (pinfunction "WB_AVSS0_33") (pintype "passive"))
      (node (ref "IC1") (pin "34") (pinfunction "WB_AVSS1_34") (pintype "passive"))
      (node (ref "IC1") (pin "42") (pinfunction "WB_AVSS2_42") (pintype "passive"))
      (node (ref "IC1") (pin "43") (pinfunction "WB_AVSS3_43") (pintype "passive"))
      (node (ref "IC1") (pin "47") (pinfunction "WB_AVSS4_47") (pintype "passive"))
      (node (ref "R1") (pin "2") (pinfunction "2_2") (pintype "passive"))
      (node (ref "R2") (pin "2") (pinfunction "2_2") (pintype "passive"))
      (node (ref "U10") (pin "2") (pinfunction "GND_2") (pintype "power_in"))
      (node (ref "U12") (pin "2") (pinfunction "GND_2") (pintype "power_in"))
      (node (ref "U13") (pin "2") (pinfunction "GND_2") (pintype "power_in"))
      (node (ref "U14") (pin "2") (pinfunction "GND_2") (pintype "power_in"))
      (node (ref "U15") (pin "2") (pinfunction "GND_2") (pintype "power_in"))
      (node (ref "U16") (pin "2") (pinfunction "GND_2") (pintype "power_in"))
      (node (ref "U2") (pin "2") (pinfunction "GND_2") (pintype "power_in"))
      (node (ref "U4") (pin "2") (pinfunction "GND_2") (pintype "power_in"))
      (node (ref "U6") (pin "2") (pinfunction "GND_2") (pintype "power_in"))
      (node (ref "U8") (pin "2") (pinfunction "GND_2") (pintype "power_in"))
      (node (ref "X2") (pin "10") (pinfunction "10_10") (pintype "passive"))
      (node (ref "X2") (pin "12") (pinfunction "12_12") (pintype "passive"))
      (node (ref "X2") (pin "14") (pinfunction "14_14") (pintype "passive"))
      (node (ref "X2") (pin "16") (pinfunction "16_16") (pintype "passive"))
      (node (ref "X2") (pin "18") (pinfunction "18_18") (pintype "passive"))
      (node (ref "X2") (pin "20") (pinfunction "20_20") (pintype "passive"))
      (node (ref "X2") (pin "21") (pinfunction "21_21") (pintype "passive"))
      (node (ref "X2") (pin "22") (pinfunction "22_22") (pintype "passive"))
      (node (ref "X2") (pin "24") (pinfunction "24_24") (pintype "passive"))
      (node (ref "X2") (pin "26") (pinfunction "26_26") (pintype "passive"))
      (node (ref "X2") (pin "28") (pinfunction "28_28") (pintype "passive"))
      (node (ref "X2") (pin "29") (pinfunction "29_29") (pintype "passive"))
      (node (ref "X2") (pin "3") (pinfunction "3_3") (pintype "passive"))
      (node (ref "X2") (pin "30") (pinfunction "30_30") (pintype "passive"))
      (node (ref "X2") (pin "32") (pinfunction "32_32") (pintype "passive"))
      (node (ref "X2") (pin "34") (pinfunction "34_34") (pintype "passive"))
      (node (ref "X2") (pin "35") (pinfunction "35_35") (pintype "passive"))
      (node (ref "X2") (pin "36") (pinfunction "36_36") (pintype "passive"))
      (node (ref "X2") (pin "38") (pinfunction "38_38") (pintype "passive"))
      (node (ref "X2") (pin "4") (pinfunction "4_4") (pintype "passive"))
      (node (ref "X2") (pin "40") (pinfunction "40_40") (pintype "passive"))
      (node (ref "X2") (pin "42") (pinfunction "42_42") (pintype "passive"))
      (node (ref "X2") (pin "44") (pinfunction "44_44") (pintype "passive"))
      (node (ref "X2") (pin "46") (pinfunction "46_46") (pintype "passive"))
      (node (ref "X2") (pin "48") (pinfunction "48_48") (pintype "passive"))
      (node (ref "X2") (pin "50") (pinfunction "50_50") (pintype "passive"))
      (node (ref "X2") (pin "7") (pinfunction "7_7") (pintype "passive"))
      (node (ref "X2") (pin "8") (pinfunction "8_8") (pintype "passive"))
    )
    (net (code "60") (name "HVDD") (class "Default")
      (node (ref "C1") (pin "1") (pinfunction "1_1") (pintype "passive"))
      (node (ref "C2") (pin "1") (pinfunction "1_1") (pintype "passive"))
      (node (ref "C3") (pin "1") (pinfunction "1_1") (pintype "passive"))
      (node (ref "C4") (pin "1") (pinfunction "1_1") (pintype "passive"))
      (node (ref "IC1") (pin "16") (pinfunction "WB_HVDD_0_16") (pintype "passive"))
      (node (ref "IC1") (pin "18") (pinfunction "WB_HVDD_1_18") (pintype "passive"))
      (node (ref "IC1") (pin "20") (pinfunction "WB_HVDD_2_20") (pintype "passive"))
      (node (ref "IC1") (pin "22") (pinfunction "WB_HVDD_3_22") (pintype "passive"))
      (node (ref "IC1") (pin "24") (pinfunction "WB_HVDD_4_24") (pintype "passive"))
      (node (ref "X1") (pin "10") (pinfunction "10_10") (pintype "passive"))
      (node (ref "X1") (pin "11") (pinfunction "11_11") (pintype "passive"))
      (node (ref "X1") (pin "12") (pinfunction "12_12") (pintype "passive"))
      (node (ref "X1") (pin "9") (pinfunction "9_9") (pintype "passive"))
    )
    (net (code "61") (name "VDD") (class "Default")
      (node (ref "C10") (pin "1") (pinfunction "1_1") (pintype "passive"))
      (node (ref "C11") (pin "1") (pinfunction "1_1") (pintype "passive"))
      (node (ref "C12") (pin "1") (pinfunction "1_1") (pintype "passive"))
      (node (ref "C17") (pin "1") (pinfunction "1_1") (pintype "passive"))
      (node (ref "C19") (pin "1") (pinfunction "1_1") (pintype "passive"))
      (node (ref "C21") (pin "1") (pinfunction "1_1") (pintype "passive"))
      (node (ref "C23") (pin "1") (pinfunction "1_1") (pintype "passive"))
      (node (ref "C25") (pin "1") (pinfunction "1_1") (pintype "passive"))
      (node (ref "C27") (pin "1") (pinfunction "1_1") (pintype "passive"))
      (node (ref "C9") (pin "1") (pinfunction "1_1") (pintype "passive"))
      (node (ref "IC1") (pin "10") (pinfunction "WB_VDD_1_10") (pintype "passive"))
      (node (ref "IC1") (pin "8") (pinfunction "WB_VDD_0_8") (pintype "passive"))
      (node (ref "U1") (pin "5") (pinfunction "VCC_5") (pintype "power_in"))
      (node (ref "U11") (pin "5") (pinfunction "VCC_5") (pintype "power_in"))
      (node (ref "U3") (pin "5") (pinfunction "VCC_5") (pintype "power_in"))
      (node (ref "U5") (pin "5") (pinfunction "VCC_5") (pintype "power_in"))
      (node (ref "U7") (pin "5") (pinfunction "VCC_5") (pintype "power_in"))
      (node (ref "U9") (pin "5") (pinfunction "VCC_5") (pintype "power_in"))
      (node (ref "X1") (pin "3") (pinfunction "3_3") (pintype "passive"))
      (node (ref "X1") (pin "4") (pinfunction "4_4") (pintype "passive"))
      (node (ref "X1") (pin "5") (pinfunction "5_5") (pintype "passive"))
      (node (ref "X1") (pin "6") (pinfunction "6_6") (pintype "passive"))
    )
    (net (code "62") (name "VPD_ANODE") (class "Default")
      (node (ref "C13") (pin "1") (pinfunction "1_1") (pintype "passive"))
      (node (ref "C14") (pin "1") (pinfunction "1_1") (pintype "passive"))
      (node (ref "C15") (pin "1") (pinfunction "1_1") (pintype "passive"))
      (node (ref "C16") (pin "1") (pinfunction "1_1") (pintype "passive"))
      (node (ref "IC1") (pin "35") (pinfunction "WB_VPD_ANODE_35") (pintype "passive"))
      (node (ref "X2") (pin "1") (pinfunction "1_1") (pintype "passive"))
      (node (ref "X2") (pin "2") (pinfunction "2_2") (pintype "passive"))
    )
    (net (code "63") (name "unconnected-(U1-CH2_IN-Pad4)") (class "Default")
      (node (ref "U1") (pin "4") (pinfunction "CH2_IN_4") (pintype "passive"))
    )
    (net (code "64") (name "unconnected-(U1-CH2_OUT-Pad6)") (class "Default")
      (node (ref "U1") (pin "6") (pinfunction "CH2_OUT_6") (pintype "passive"))
    )
    (net (code "65") (name "unconnected-(U8-CH2_IN-Pad4)") (class "Default")
      (node (ref "U8") (pin "4") (pinfunction "CH2_IN_4") (pintype "passive+no_connect"))
    )
    (net (code "66") (name "unconnected-(U8-CH2_OUT-Pad6)") (class "Default")
      (node (ref "U8") (pin "6") (pinfunction "CH2_OUT_6") (pintype "passive+no_connect"))
    )
    (net (code "67") (name "unconnected-(U13-CH2_IN-Pad4)") (class "Default")
      (node (ref "U13") (pin "4") (pinfunction "CH2_IN_4") (pintype "passive"))
    )
    (net (code "68") (name "unconnected-(U13-CH2_OUT-Pad6)") (class "Default")
      (node (ref "U13") (pin "6") (pinfunction "CH2_OUT_6") (pintype "passive"))
    )
  )
)
